# HW2_latest_v2.net
KiCad netlist of a schematic drawn in EAGLE
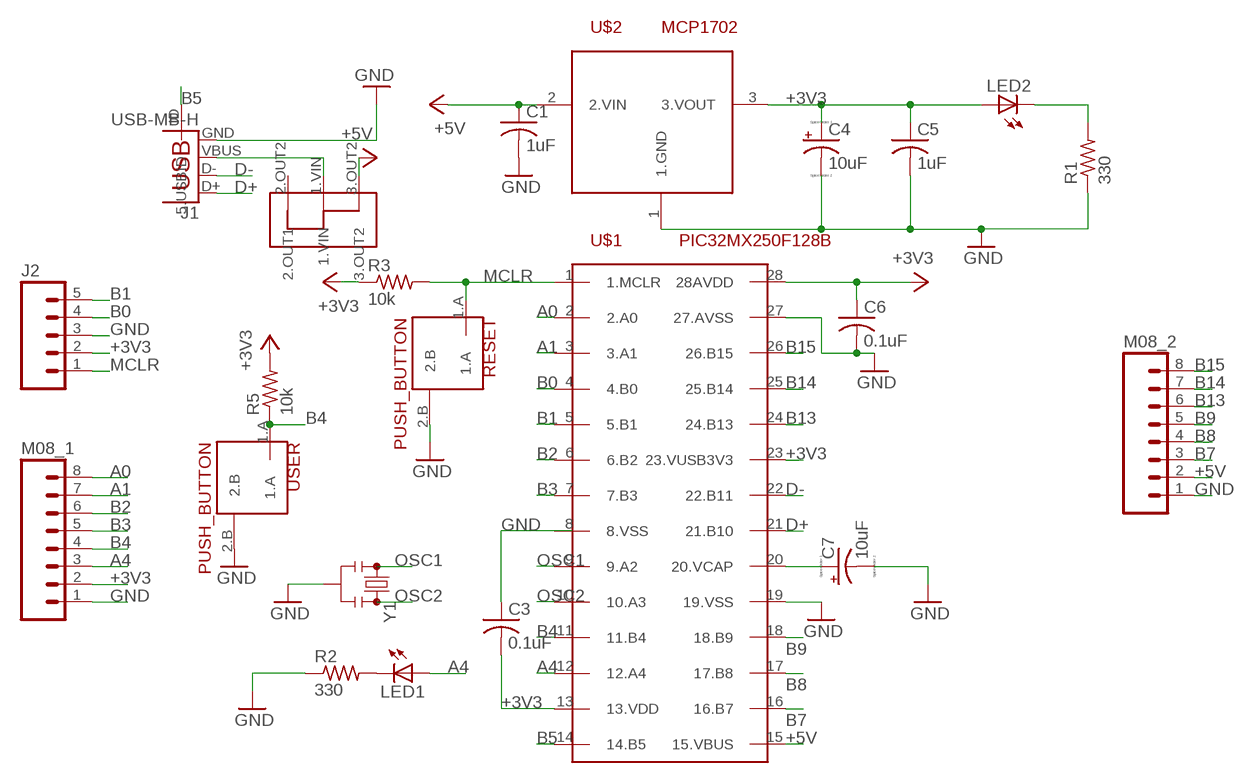
[diagram p0: schematic, sheet 1]

(export (version "E")
  (design (tool "Eeschema 10.0.6"))
  (components
    (comp (ref "C1")
      (value "1uF")
      (footprint "eagle-import:C025-024X044")
      (libsource (lib "eagle-import") (part "C-US025-024X044"))
    )
    (comp (ref "C3")
      (value "0.1uF")
      (footprint "eagle-import:C025-024X044")
      (libsource (lib "eagle-import") (part "C-US025-024X044"))
    )
    (comp (ref "C4")
      (value "10uF")
      (footprint "eagle-import:TT2D4")
      (libsource (lib "eagle-import") (part "CPOL-USTT2D4"))
    )
    (comp (ref "C5")
      (value "1uF")
      (footprint "eagle-import:C025-024X044")
      (libsource (lib "eagle-import") (part "C-US025-024X044"))
    )
    (comp (ref "C6")
      (value "0.1uF")
      (footprint "eagle-import:C025-024X044")
      (libsource (lib "eagle-import") (part "C-US025-024X044"))
    )
    (comp (ref "C7")
      (value "10uF")
      (footprint "eagle-import:TT2D4")
      (libsource (lib "eagle-import") (part "CPOL-USTT2D4"))
    )
    (comp (ref "J1")
      (value "USB-MB-H")
      (footprint "eagle-import:USB-MB-H")
      (libsource (lib "eagle-import") (part "USB-MB-H"))
    )
    (comp (ref "J2")
      (value "M05PTH")
      (footprint "eagle-import:1X05")
      (libsource (lib "eagle-import") (part "M05PTH"))
    )
    (comp (ref "LED1")
      (value "LED3MM")
      (footprint "eagle-import:LED3MM")
      (libsource (lib "eagle-import") (part "LED3MM"))
    )
    (comp (ref "LED2")
      (value "LED3MM")
      (footprint "eagle-import:LED3MM")
      (libsource (lib "eagle-import") (part "LED3MM"))
    )
    (comp (ref "M08_1")
      (value "M08")
      (footprint "eagle-import:1X08_ROUND")
      (libsource (lib "eagle-import") (part "M08"))
    )
    (comp (ref "M08_2")
      (value "M08")
      (footprint "eagle-import:1X08_ROUND")
      (libsource (lib "eagle-import") (part "M08"))
    )
    (comp (ref "R1")
      (value "330")
      (footprint "eagle-import:0207_10")
      (libsource (lib "eagle-import") (part "R-US_0207/10"))
    )
    (comp (ref "R2")
      (value "330")
      (footprint "eagle-import:0207_10")
      (libsource (lib "eagle-import") (part "R-US_0207/10"))
    )
    (comp (ref "R3")
      (value "10k")
      (footprint "eagle-import:0207_10")
      (libsource (lib "eagle-import") (part "R-US_0207/10"))
    )
    (comp (ref "R5")
      (value "10k")
      (footprint "eagle-import:0207_10")
      (libsource (lib "eagle-import") (part "R-US_0207/10"))
    )
    (comp (ref "RESET")
      (value "PUSH_BUTTON")
      (footprint "eagle-import:PUSH_BUTTON")
      (libsource (lib "eagle-import") (part "PUSH_BUTTON"))
    )
    (comp (ref "U$1")
      (value "PIC32MX250F128B")
      (footprint "eagle-import:DIL28-3")
      (libsource (lib "eagle-import") (part "PIC32"))
    )
    (comp (ref "U$2")
      (value "MCP1702")
      (footprint "eagle-import:TO92")
      (libsource (lib "eagle-import") (part "MCP1702"))
    )
    (comp (ref "U$3")
      (value "SLIDE_SWITCH")
      (footprint "eagle-import:SLIDE_SWITCH")
      (libsource (lib "eagle-import") (part "SLIDE_SWITCH"))
    )
    (comp (ref "USER")
      (value "PUSH_BUTTON")
      (footprint "eagle-import:PUSH_BUTTON")
      (libsource (lib "eagle-import") (part "PUSH_BUTTON"))
    )
    (comp (ref "Y1")
      (value "RESONATORPTH")
      (footprint "eagle-import:RESONATOR-PTH")
      (libsource (lib "eagle-import") (part "RESONATORPTH"))
    )
  )
  (nets
    (net (code "1") (name "+3V3") (class "Default")
      (node (ref "C3") (pin "2") (pinfunction "2_2") (pintype "passive"))
      (node (ref "C4") (pin "+") (pinfunction "+_+") (pintype "passive"))
      (node (ref "C5") (pin "1") (pinfunction "1_1") (pintype "passive"))
      (node (ref "C6") (pin "1") (pinfunction "1_1") (pintype "passive"))
      (node (ref "J2") (pin "2") (pinfunction "2_2") (pintype "passive"))
      (node (ref "LED2") (pin "A") (pinfunction "A_A") (pintype "passive"))
      (node (ref "M08_1") (pin "2") (pinfunction "2_2") (pintype "passive"))
      (node (ref "R3") (pin "1") (pinfunction "1_1") (pintype "passive"))
      (node (ref "R5") (pin "2") (pinfunction "2_2") (pintype "passive"))
      (node (ref "U$1") (pin "13") (pinfunction "13.VDD_13") (pintype "bidirectional"))
      (node (ref "U$1") (pin "23") (pinfunction "23.VUSB3V3_23") (pintype "bidirectional"))
      (node (ref "U$1") (pin "28") (pinfunction "28AVDD_28") (pintype "bidirectional"))
      (node (ref "U$2") (pin "3") (pinfunction "3.VOUT_3") (pintype "bidirectional"))
    )
    (net (code "2") (name "+5V") (class "Default")
      (node (ref "C1") (pin "1") (pinfunction "1_1") (pintype "passive"))
      (node (ref "M08_2") (pin "2") (pinfunction "2_2") (pintype "passive"))
      (node (ref "U$1") (pin "15") (pinfunction "15.VBUS_15") (pintype "bidirectional"))
      (node (ref "U$2") (pin "2") (pinfunction "2.VIN_2") (pintype "bidirectional"))
      (node (ref "U$3") (pin "3.OUT2") (pinfunction "3.OUT2_3.OUT2") (pintype "bidirectional"))
    )
    (net (code "3") (name "/A0") (class "Default")
      (node (ref "M08_1") (pin "8") (pinfunction "8_8") (pintype "passive"))
      (node (ref "U$1") (pin "2") (pinfunction "2.A0_2") (pintype "bidirectional"))
    )
    (net (code "4") (name "/A1") (class "Default")
      (node (ref "M08_1") (pin "7") (pinfunction "7_7") (pintype "passive"))
      (node (ref "U$1") (pin "3") (pinfunction "3.A1_3") (pintype "bidirectional"))
    )
    (net (code "5") (name "/A4") (class "Default")
      (node (ref "LED1") (pin "A") (pinfunction "A_A") (pintype "passive"))
      (node (ref "M08_1") (pin "3") (pinfunction "3_3") (pintype "passive"))
      (node (ref "U$1") (pin "12") (pinfunction "12.A4_12") (pintype "bidirectional"))
    )
    (net (code "6") (name "/B0") (class "Default")
      (node (ref "J2") (pin "4") (pinfunction "4_4") (pintype "passive"))
      (node (ref "U$1") (pin "4") (pinfunction "4.B0_4") (pintype "bidirectional"))
    )
    (net (code "7") (name "/B1") (class "Default")
      (node (ref "J2") (pin "5") (pinfunction "5_5") (pintype "passive"))
      (node (ref "U$1") (pin "5") (pinfunction "5.B1_5") (pintype "bidirectional"))
    )
    (net (code "8") (name "/B2") (class "Default")
      (node (ref "M08_1") (pin "6") (pinfunction "6_6") (pintype "passive"))
      (node (ref "U$1") (pin "6") (pinfunction "6.B2_6") (pintype "bidirectional"))
    )
    (net (code "9") (name "/B3") (class "Default")
      (node (ref "M08_1") (pin "5") (pinfunction "5_5") (pintype "passive"))
      (node (ref "U$1") (pin "7") (pinfunction "7.B3_7") (pintype "bidirectional"))
    )
    (net (code "10") (name "/B4") (class "Default")
      (node (ref "M08_1") (pin "4") (pinfunction "4_4") (pintype "passive"))
      (node (ref "R5") (pin "1") (pinfunction "1_1") (pintype "passive"))
      (node (ref "U$1") (pin "11") (pinfunction "11.B4_11") (pintype "bidirectional"))
      (node (ref "USER") (pin "1.A") (pinfunction "1.A_1.A") (pintype "bidirectional"))
    )
    (net (code "11") (name "/B5") (class "Default")
      (node (ref "J1") (pin "ID") (pinfunction "5.USBID_ID") (pintype "bidirectional"))
      (node (ref "U$1") (pin "14") (pinfunction "14.B5_14") (pintype "bidirectional"))
    )
    (net (code "12") (name "/B7") (class "Default")
      (node (ref "M08_2") (pin "3") (pinfunction "3_3") (pintype "passive"))
      (node (ref "U$1") (pin "16") (pinfunction "16.B7_16") (pintype "bidirectional"))
    )
    (net (code "13") (name "/B8") (class "Default")
      (node (ref "M08_2") (pin "4") (pinfunction "4_4") (pintype "passive"))
      (node (ref "U$1") (pin "17") (pinfunction "17.B8_17") (pintype "bidirectional"))
    )
    (net (code "14") (name "/B9") (class "Default")
      (node (ref "M08_2") (pin "5") (pinfunction "5_5") (pintype "passive"))
      (node (ref "U$1") (pin "18") (pinfunction "18.B9_18") (pintype "bidirectional"))
    )
    (net (code "15") (name "/B13") (class "Default")
      (node (ref "M08_2") (pin "6") (pinfunction "6_6") (pintype "passive"))
      (node (ref "U$1") (pin "24") (pinfunction "24.B13_24") (pintype "bidirectional"))
    )
    (net (code "16") (name "/B14") (class "Default")
      (node (ref "M08_2") (pin "7") (pinfunction "7_7") (pintype "passive"))
      (node (ref "U$1") (pin "25") (pinfunction "25.B14_25") (pintype "bidirectional"))
    )
    (net (code "17") (name "/B15") (class "Default")
      (node (ref "M08_2") (pin "8") (pinfunction "8_8") (pintype "passive"))
      (node (ref "U$1") (pin "26") (pinfunction "26.B15_26") (pintype "bidirectional"))
    )
    (net (code "18") (name "/D+") (class "Default")
      (node (ref "J1") (pin "D+") (pinfunction "D+_D+") (pintype "bidirectional"))
      (node (ref "U$1") (pin "21") (pinfunction "21.B10_21") (pintype "bidirectional"))
    )
    (net (code "19") (name "/D-") (class "Default")
      (node (ref "J1") (pin "D-") (pinfunction "D-_D-") (pintype "bidirectional"))
      (node (ref "U$1") (pin "22") (pinfunction "22.B11_22") (pintype "bidirectional"))
    )
    (net (code "20") (name "/MCLR") (class "Default")
      (node (ref "J2") (pin "1") (pinfunction "1_1") (pintype "passive"))
      (node (ref "R3") (pin "2") (pinfunction "2_2") (pintype "passive"))
      (node (ref "RESET") (pin "1.A") (pinfunction "1.A_1.A") (pintype "bidirectional"))
      (node (ref "U$1") (pin "1") (pinfunction "1.MCLR_1") (pintype "bidirectional"))
    )
    (net (code "21") (name "/OSC1") (class "Default")
      (node (ref "U$1") (pin "9") (pinfunction "9.A2_9") (pintype "bidirectional"))
      (node (ref "Y1") (pin "1") (pinfunction "1_1") (pintype "passive"))
    )
    (net (code "22") (name "/OSC2") (class "Default")
      (node (ref "U$1") (pin "10") (pinfunction "10.A3_10") (pintype "bidirectional"))
      (node (ref "Y1") (pin "3") (pinfunction "3_3") (pintype "passive"))
    )
    (net (code "23") (name "GND") (class "Default")
      (node (ref "C1") (pin "2") (pinfunction "2_2") (pintype "passive"))
      (node (ref "C3") (pin "1") (pinfunction "1_1") (pintype "passive"))
      (node (ref "C4") (pin "-") (pinfunction "-_-") (pintype "passive"))
      (node (ref "C5") (pin "2") (pinfunction "2_2") (pintype "passive"))
      (node (ref "C6") (pin "2") (pinfunction "2_2") (pintype "passive"))
      (node (ref "C7") (pin "-") (pinfunction "-_-") (pintype "passive"))
      (node (ref "J1") (pin "GND") (pinfunction "GND_GND") (pintype "bidirectional"))
      (node (ref "J2") (pin "3") (pinfunction "3_3") (pintype "passive"))
      (node (ref "M08_1") (pin "1") (pinfunction "1_1") (pintype "passive"))
      (node (ref "M08_2") (pin "1") (pinfunction "1_1") (pintype "passive"))
      (node (ref "R1") (pin "1") (pinfunction "1_1") (pintype "passive"))
      (node (ref "R2") (pin "1") (pinfunction "1_1") (pintype "passive"))
      (node (ref "RESET") (pin "2.B") (pinfunction "2.B_2.B") (pintype "bidirectional"))
      (node (ref "U$1") (pin "19") (pinfunction "19.VSS_19") (pintype "bidirectional"))
      (node (ref "U$1") (pin "27") (pinfunction "27.AVSS_27") (pintype "bidirectional"))
      (node (ref "U$2") (pin "1") (pinfunction "1.GND_1") (pintype "bidirectional"))
      (node (ref "USER") (pin "2.B") (pinfunction "2.B_2.B") (pintype "bidirectional"))
      (node (ref "Y1") (pin "2") (pinfunction "2_2") (pintype "passive"))
    )
    (net (code "24") (name "Net-(J1-PadVBUS)") (class "Default")
      (node (ref "J1") (pin "VBUS") (pinfunction "VBUS_VBUS") (pintype "bidirectional"))
      (node (ref "U$3") (pin "1.VIN") (pinfunction "1.VIN_1.VIN") (pintype "bidirectional"))
    )
    (net (code "25") (name "Net-(LED1-C)") (class "Default")
      (node (ref "LED1") (pin "K") (pinfunction "C_K") (pintype "passive"))
      (node (ref "R2") (pin "2") (pinfunction "2_2") (pintype "passive"))
    )
    (net (code "26") (name "Net-(LED2-C)") (class "Default")
      (node (ref "LED2") (pin "K") (pinfunction "C_K") (pintype "passive"))
      (node (ref "R1") (pin "2") (pinfunction "2_2") (pintype "passive"))
    )
    (net (code "27") (name "Net-(U$1-20.VCAP)") (class "Default")
      (node (ref "C7") (pin "+") (pinfunction "+_+") (pintype "passive"))
      (node (ref "U$1") (pin "20") (pinfunction "20.VCAP_20") (pintype "bidirectional"))
    )
    (net (code "28") (name "unconnected-(U$1-8.VSS-Pad8)") (class "Default")
      (node (ref "U$1") (pin "8") (pinfunction "8.VSS_8") (pintype "bidirectional"))
    )
    (net (code "29") (name "unconnected-(U$3-2.OUT1-Pad2.OUT2)") (class "Default")
      (node (ref "U$3") (pin "2.OUT2") (pinfunction "2.OUT1_2.OUT2") (pintype "bidirectional"))
    )
  )
)
